# QuadQuantizer.net
KiCad netlist of a schematic drawn in EAGLE
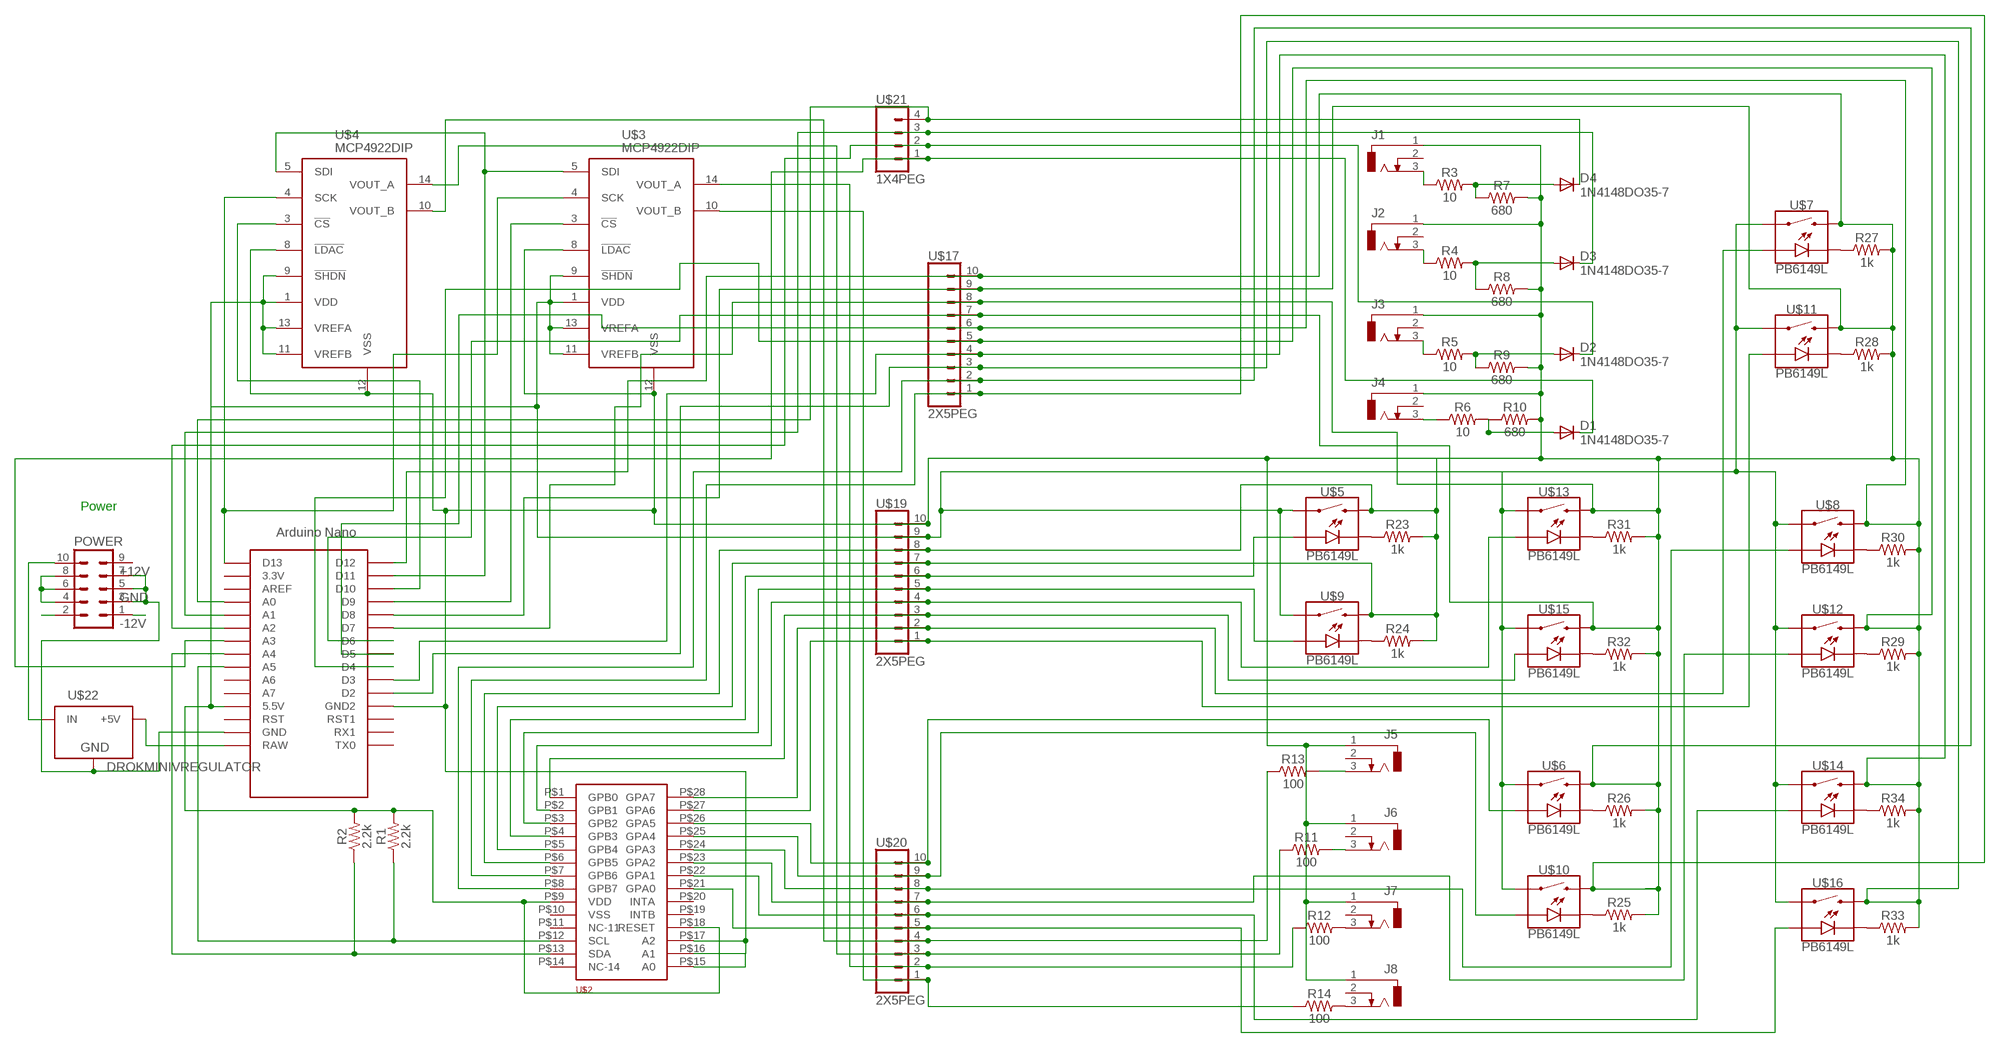
[diagram p0: schematic, sheet 1]

(export (version "E")
  (design (tool "Eeschema 10.0.6"))
  (components
    (comp (ref "D1")
      (value "1N4148DO35-7")
      (footprint "eagle-import:DO35-7")
      (libsource (lib "eagle-import") (part "1N4148DO35-7"))
    )
    (comp (ref "D2")
      (value "1N4148DO35-7")
      (footprint "eagle-import:DO35-7")
      (libsource (lib "eagle-import") (part "1N4148DO35-7"))
    )
    (comp (ref "D3")
      (value "1N4148DO35-7")
      (footprint "eagle-import:DO35-7")
      (libsource (lib "eagle-import") (part "1N4148DO35-7"))
    )
    (comp (ref "D4")
      (value "1N4148DO35-7")
      (footprint "eagle-import:DO35-7")
      (libsource (lib "eagle-import") (part "1N4148DO35-7"))
    )
    (comp (ref "J1")
      (value "THONK35A")
      (footprint "eagle-import:THONK35A")
      (libsource (lib "eagle-import") (part "THONK35A"))
    )
    (comp (ref "J2")
      (value "THONK35A")
      (footprint "eagle-import:THONK35A")
      (libsource (lib "eagle-import") (part "THONK35A"))
    )
    (comp (ref "J3")
      (value "THONK35A")
      (footprint "eagle-import:THONK35A")
      (libsource (lib "eagle-import") (part "THONK35A"))
    )
    (comp (ref "J4")
      (value "THONK35A")
      (footprint "eagle-import:THONK35A")
      (libsource (lib "eagle-import") (part "THONK35A"))
    )
    (comp (ref "J5")
      (value "THONK35A")
      (footprint "eagle-import:THONK35A")
      (libsource (lib "eagle-import") (part "THONK35A"))
    )
    (comp (ref "J6")
      (value "THONK35A")
      (footprint "eagle-import:THONK35A")
      (libsource (lib "eagle-import") (part "THONK35A"))
    )
    (comp (ref "J7")
      (value "THONK35A")
      (footprint "eagle-import:THONK35A")
      (libsource (lib "eagle-import") (part "THONK35A"))
    )
    (comp (ref "J8")
      (value "THONK35A")
      (footprint "eagle-import:THONK35A")
      (libsource (lib "eagle-import") (part "THONK35A"))
    )
    (comp (ref "POWER")
      (value "10_PIN_HEADER")
      (footprint "eagle-import:MA05-2")
      (libsource (lib "eagle-import") (part "10_PIN_HEADER"))
    )
    (comp (ref "R1")
      (value "2.2k")
      (footprint "eagle-import:AXIAL-0.3")
      (libsource (lib "eagle-import") (part "1KOHM-HORIZ-1/4W-1%"))
    )
    (comp (ref "R2")
      (value "2.2k")
      (footprint "eagle-import:AXIAL-0.3")
      (libsource (lib "eagle-import") (part "1KOHM-HORIZ-1/4W-1%"))
    )
    (comp (ref "R3")
      (value "10")
      (footprint "eagle-import:AXIAL-0.3")
      (libsource (lib "eagle-import") (part "10OHM-HORIZ-1/4W-1%"))
    )
    (comp (ref "R4")
      (value "10")
      (footprint "eagle-import:AXIAL-0.3")
      (libsource (lib "eagle-import") (part "10OHM-HORIZ-1/4W-1%"))
    )
    (comp (ref "R5")
      (value "10")
      (footprint "eagle-import:AXIAL-0.3")
      (libsource (lib "eagle-import") (part "10OHM-HORIZ-1/4W-1%"))
    )
    (comp (ref "R6")
      (value "10")
      (footprint "eagle-import:AXIAL-0.3")
      (libsource (lib "eagle-import") (part "10OHM-HORIZ-1/4W-1%"))
    )
    (comp (ref "R7")
      (value "680")
      (footprint "eagle-import:AXIAL-0.3")
      (libsource (lib "eagle-import") (part "10OHM-HORIZ-1/4W-1%"))
    )
    (comp (ref "R8")
      (value "680")
      (footprint "eagle-import:AXIAL-0.3")
      (libsource (lib "eagle-import") (part "10OHM-HORIZ-1/4W-1%"))
    )
    (comp (ref "R9")
      (value "680")
      (footprint "eagle-import:AXIAL-0.3")
      (libsource (lib "eagle-import") (part "10OHM-HORIZ-1/4W-1%"))
    )
    (comp (ref "R10")
      (value "680")
      (footprint "eagle-import:AXIAL-0.3")
      (libsource (lib "eagle-import") (part "10OHM-HORIZ-1/4W-1%"))
    )
    (comp (ref "R11")
      (value "100")
      (footprint "eagle-import:AXIAL-0.3")
      (libsource (lib "eagle-import") (part "100OHM-HORIZ-1/4W-1%"))
    )
    (comp (ref "R12")
      (value "100")
      (footprint "eagle-import:AXIAL-0.3")
      (libsource (lib "eagle-import") (part "100OHM-HORIZ-1/4W-1%"))
    )
    (comp (ref "R13")
      (value "100")
      (footprint "eagle-import:AXIAL-0.3")
      (libsource (lib "eagle-import") (part "100OHM-HORIZ-1/4W-1%"))
    )
    (comp (ref "R14")
      (value "100")
      (footprint "eagle-import:AXIAL-0.3")
      (libsource (lib "eagle-import") (part "100OHM-HORIZ-1/4W-1%"))
    )
    (comp (ref "R23")
      (value "1k")
      (footprint "eagle-import:AXIAL-0.3")
      (libsource (lib "eagle-import") (part "1KOHM-HORIZ-1/4W-1%"))
    )
    (comp (ref "R24")
      (value "1k")
      (footprint "eagle-import:AXIAL-0.3")
      (libsource (lib "eagle-import") (part "1KOHM-HORIZ-1/4W-1%"))
    )
    (comp (ref "R25")
      (value "1k")
      (footprint "eagle-import:AXIAL-0.3")
      (libsource (lib "eagle-import") (part "1KOHM-HORIZ-1/4W-1%"))
    )
    (comp (ref "R26")
      (value "1k")
      (footprint "eagle-import:AXIAL-0.3")
      (libsource (lib "eagle-import") (part "1KOHM-HORIZ-1/4W-1%"))
    )
    (comp (ref "R27")
      (value "1k")
      (footprint "eagle-import:AXIAL-0.3")
      (libsource (lib "eagle-import") (part "1KOHM-HORIZ-1/4W-1%"))
    )
    (comp (ref "R28")
      (value "1k")
      (footprint "eagle-import:AXIAL-0.3")
      (libsource (lib "eagle-import") (part "1KOHM-HORIZ-1/4W-1%"))
    )
    (comp (ref "R29")
      (value "1k")
      (footprint "eagle-import:AXIAL-0.3")
      (libsource (lib "eagle-import") (part "1KOHM-HORIZ-1/4W-1%"))
    )
    (comp (ref "R30")
      (value "1k")
      (footprint "eagle-import:AXIAL-0.3")
      (libsource (lib "eagle-import") (part "1KOHM-HORIZ-1/4W-1%"))
    )
    (comp (ref "R31")
      (value "1k")
      (footprint "eagle-import:AXIAL-0.3")
      (libsource (lib "eagle-import") (part "1KOHM-HORIZ-1/4W-1%"))
    )
    (comp (ref "R32")
      (value "1k")
      (footprint "eagle-import:AXIAL-0.3")
      (libsource (lib "eagle-import") (part "1KOHM-HORIZ-1/4W-1%"))
    )
    (comp (ref "R33")
      (value "1k")
      (footprint "eagle-import:AXIAL-0.3")
      (libsource (lib "eagle-import") (part "1KOHM-HORIZ-1/4W-1%"))
    )
    (comp (ref "R34")
      (value "1k")
      (footprint "eagle-import:AXIAL-0.3")
      (libsource (lib "eagle-import") (part "1KOHM-HORIZ-1/4W-1%"))
    )
    (comp (ref "U$1")
      (value "NANO")
      (footprint "eagle-import:NANO")
      (libsource (lib "eagle-import") (part "NANO"))
    )
    (comp (ref "U$2")
      (value "MCP23017-E/SP")
      (footprint "eagle-import:DIP28")
      (libsource (lib "eagle-import") (part "MCP23017-E/SP"))
    )
    (comp (ref "U$3")
      (value "MCP4922DIP")
      (footprint "eagle-import:EDG-07")
      (libsource (lib "eagle-import") (part "MCP4922DIP"))
    )
    (comp (ref "U$4")
      (value "MCP4922DIP")
      (footprint "eagle-import:EDG-07")
      (libsource (lib "eagle-import") (part "MCP4922DIP"))
    )
    (comp (ref "U$5")
      (value "PB6149L")
      (footprint "eagle-import:PB6149L")
      (libsource (lib "eagle-import") (part "PB6149L"))
    )
    (comp (ref "U$6")
      (value "PB6149L")
      (footprint "eagle-import:PB6149L")
      (libsource (lib "eagle-import") (part "PB6149L"))
    )
    (comp (ref "U$7")
      (value "PB6149L")
      (footprint "eagle-import:PB6149L")
      (libsource (lib "eagle-import") (part "PB6149L"))
    )
    (comp (ref "U$8")
      (value "PB6149L")
      (footprint "eagle-import:PB6149L")
      (libsource (lib "eagle-import") (part "PB6149L"))
    )
    (comp (ref "U$9")
      (value "PB6149L")
      (footprint "eagle-import:PB6149L")
      (libsource (lib "eagle-import") (part "PB6149L"))
    )
    (comp (ref "U$10")
      (value "PB6149L")
      (footprint "eagle-import:PB6149L")
      (libsource (lib "eagle-import") (part "PB6149L"))
    )
    (comp (ref "U$11")
      (value "PB6149L")
      (footprint "eagle-import:PB6149L")
      (libsource (lib "eagle-import") (part "PB6149L"))
    )
    (comp (ref "U$12")
      (value "PB6149L")
      (footprint "eagle-import:PB6149L")
      (libsource (lib "eagle-import") (part "PB6149L"))
    )
    (comp (ref "U$13")
      (value "PB6149L")
      (footprint "eagle-import:PB6149L")
      (libsource (lib "eagle-import") (part "PB6149L"))
    )
    (comp (ref "U$14")
      (value "PB6149L")
      (footprint "eagle-import:PB6149L")
      (libsource (lib "eagle-import") (part "PB6149L"))
    )
    (comp (ref "U$15")
      (value "PB6149L")
      (footprint "eagle-import:PB6149L")
      (libsource (lib "eagle-import") (part "PB6149L"))
    )
    (comp (ref "U$16")
      (value "PB6149L")
      (footprint "eagle-import:PB6149L")
      (libsource (lib "eagle-import") (part "PB6149L"))
    )
    (comp (ref "U$17")
      (value "2X5PEG")
      (footprint "eagle-import:2X5")
      (libsource (lib "eagle-import") (part "2X5PEG"))
    )
    (comp (ref "U$19")
      (value "2X5PEG")
      (footprint "eagle-import:2X5")
      (libsource (lib "eagle-import") (part "2X5PEG"))
    )
    (comp (ref "U$20")
      (value "2X5PEG")
      (footprint "eagle-import:2X5")
      (libsource (lib "eagle-import") (part "2X5PEG"))
    )
    (comp (ref "U$21")
      (value "1X4PEG")
      (footprint "eagle-import:1X04")
      (libsource (lib "eagle-import") (part "1X4PEG"))
    )
    (comp (ref "U$22")
      (value "DROKMINIVREGULATOR")
      (footprint "eagle-import:1X04")
      (libsource (lib "eagle-import") (part "DROKMINIVREGULATOR"))
    )
  )
  (nets
    (net (code "1") (name "+12V") (class "Default")
      (node (ref "POWER") (pin "10") (pinfunction "10_10") (pintype "passive"))
      (node (ref "U$22") (pin "2") (pinfunction "IN_2") (pintype "power_in"))
    )
    (net (code "2") (name "-12V") (class "Default")
      (node (ref "POWER") (pin "1") (pinfunction "1_1") (pintype "passive"))
      (node (ref "POWER") (pin "2") (pinfunction "2_2") (pintype "passive"))
    )
    (net (code "3") (name "GND") (class "Default")
      (node (ref "POWER") (pin "3") (pinfunction "3_3") (pintype "passive"))
      (node (ref "POWER") (pin "4") (pinfunction "4_4") (pintype "passive"))
      (node (ref "POWER") (pin "5") (pinfunction "5_5") (pintype "passive"))
      (node (ref "POWER") (pin "6") (pinfunction "6_6") (pintype "passive"))
      (node (ref "POWER") (pin "7") (pinfunction "7_7") (pintype "passive"))
      (node (ref "POWER") (pin "8") (pinfunction "8_8") (pintype "passive"))
      (node (ref "U$1") (pin "GND") (pinfunction "GND_GND") (pintype "bidirectional"))
      (node (ref "U$22") (pin "3") (pinfunction "GND_3") (pintype "power_in"))
    )
    (net (code "4") (name "Net-(D1-PadC)") (class "Default")
      (node (ref "D1") (pin "C") (pinfunction "C_C") (pintype "passive"))
      (node (ref "U$1") (pin "A3") (pinfunction "A3_A3") (pintype "bidirectional"))
      (node (ref "U$21") (pin "1") (pinfunction "1_1") (pintype "passive"))
    )
    (net (code "5") (name "Net-(D2-PadC)") (class "Default")
      (node (ref "D2") (pin "C") (pinfunction "C_C") (pintype "passive"))
      (node (ref "U$1") (pin "A2") (pinfunction "A2_A2") (pintype "bidirectional"))
      (node (ref "U$21") (pin "2") (pinfunction "2_2") (pintype "passive"))
    )
    (net (code "6") (name "Net-(D3-PadC)") (class "Default")
      (node (ref "D3") (pin "C") (pinfunction "C_C") (pintype "passive"))
      (node (ref "U$1") (pin "A1") (pinfunction "A1_A1") (pintype "bidirectional"))
      (node (ref "U$21") (pin "3") (pinfunction "3_3") (pintype "passive"))
    )
    (net (code "7") (name "Net-(D4-PadC)") (class "Default")
      (node (ref "D4") (pin "C") (pinfunction "C_C") (pintype "passive"))
      (node (ref "U$1") (pin "A0") (pinfunction "A0_A0") (pintype "bidirectional"))
      (node (ref "U$21") (pin "4") (pinfunction "4_4") (pintype "passive"))
    )
    (net (code "8") (name "Net-(R1-1)") (class "Default")
      (node (ref "R1") (pin "P$1") (pinfunction "1_P$1") (pintype "passive"))
      (node (ref "U$1") (pin "A5") (pinfunction "A5_A5") (pintype "bidirectional"))
      (node (ref "U$2") (pin "P$12") (pinfunction "SCL_P$12") (pintype "bidirectional"))
    )
    (net (code "9") (name "Net-(R1-2)") (class "Default")
      (node (ref "R1") (pin "P$2") (pinfunction "2_P$2") (pintype "passive"))
      (node (ref "R2") (pin "P$2") (pinfunction "2_P$2") (pintype "passive"))
      (node (ref "U$1") (pin "5V") (pinfunction "5.5V_5V") (pintype "bidirectional"))
      (node (ref "U$10") (pin "P$1") (pinfunction "1_P$1") (pintype "passive"))
      (node (ref "U$11") (pin "P$1") (pinfunction "1_P$1") (pintype "passive"))
      (node (ref "U$12") (pin "P$1") (pinfunction "1_P$1") (pintype "passive"))
      (node (ref "U$13") (pin "P$1") (pinfunction "1_P$1") (pintype "passive"))
      (node (ref "U$14") (pin "P$1") (pinfunction "1_P$1") (pintype "passive"))
      (node (ref "U$15") (pin "P$1") (pinfunction "1_P$1") (pintype "passive"))
      (node (ref "U$16") (pin "P$1") (pinfunction "1_P$1") (pintype "passive"))
      (node (ref "U$19") (pin "9") (pinfunction "9_9") (pintype "passive"))
      (node (ref "U$2") (pin "P$18") (pinfunction "RESET_P$18") (pintype "bidirectional"))
      (node (ref "U$2") (pin "P$9") (pinfunction "VDD_P$9") (pintype "bidirectional"))
      (node (ref "U$3") (pin "1") (pinfunction "VDD_1") (pintype "bidirectional"))
      (node (ref "U$3") (pin "11") (pinfunction "VREFB_11") (pintype "bidirectional"))
      (node (ref "U$3") (pin "13") (pinfunction "VREFA_13") (pintype "bidirectional"))
      (node (ref "U$3") (pin "9") (pinfunction "~{SHDN}_9") (pintype "bidirectional"))
      (node (ref "U$4") (pin "1") (pinfunction "VDD_1") (pintype "bidirectional"))
      (node (ref "U$4") (pin "11") (pinfunction "VREFB_11") (pintype "bidirectional"))
      (node (ref "U$4") (pin "13") (pinfunction "VREFA_13") (pintype "bidirectional"))
      (node (ref "U$4") (pin "9") (pinfunction "~{SHDN}_9") (pintype "bidirectional"))
      (node (ref "U$5") (pin "P$1") (pinfunction "1_P$1") (pintype "passive"))
      (node (ref "U$6") (pin "P$1") (pinfunction "1_P$1") (pintype "passive"))
      (node (ref "U$7") (pin "P$1") (pinfunction "1_P$1") (pintype "passive"))
      (node (ref "U$8") (pin "P$1") (pinfunction "1_P$1") (pintype "passive"))
      (node (ref "U$9") (pin "P$1") (pinfunction "1_P$1") (pintype "passive"))
    )
    (net (code "10") (name "Net-(R2-1)") (class "Default")
      (node (ref "R2") (pin "P$1") (pinfunction "1_P$1") (pintype "passive"))
      (node (ref "U$1") (pin "A4") (pinfunction "A4_A4") (pintype "bidirectional"))
      (node (ref "U$2") (pin "P$13") (pinfunction "SDA_P$13") (pintype "bidirectional"))
    )
    (net (code "11") (name "Net-(R3-1)") (class "Default")
      (node (ref "J1") (pin "3") (pinfunction "3_3") (pintype "passive"))
      (node (ref "R3") (pin "P$1") (pinfunction "1_P$1") (pintype "passive"))
    )
    (net (code "12") (name "Net-(R3-2)") (class "Default")
      (node (ref "D4") (pin "A") (pinfunction "A_A") (pintype "passive"))
      (node (ref "R3") (pin "P$2") (pinfunction "2_P$2") (pintype "passive"))
      (node (ref "R7") (pin "P$1") (pinfunction "1_P$1") (pintype "passive"))
    )
    (net (code "13") (name "Net-(R4-1)") (class "Default")
      (node (ref "J2") (pin "3") (pinfunction "3_3") (pintype "passive"))
      (node (ref "R4") (pin "P$1") (pinfunction "1_P$1") (pintype "passive"))
    )
    (net (code "14") (name "Net-(R4-2)") (class "Default")
      (node (ref "D3") (pin "A") (pinfunction "A_A") (pintype "passive"))
      (node (ref "R4") (pin "P$2") (pinfunction "2_P$2") (pintype "passive"))
      (node (ref "R8") (pin "P$1") (pinfunction "1_P$1") (pintype "passive"))
    )
    (net (code "15") (name "Net-(R5-1)") (class "Default")
      (node (ref "J3") (pin "3") (pinfunction "3_3") (pintype "passive"))
      (node (ref "R5") (pin "P$1") (pinfunction "1_P$1") (pintype "passive"))
    )
    (net (code "16") (name "Net-(R5-2)") (class "Default")
      (node (ref "D2") (pin "A") (pinfunction "A_A") (pintype "passive"))
      (node (ref "R5") (pin "P$2") (pinfunction "2_P$2") (pintype "passive"))
      (node (ref "R9") (pin "P$1") (pinfunction "1_P$1") (pintype "passive"))
    )
    (net (code "17") (name "Net-(R6-1)") (class "Default")
      (node (ref "J4") (pin "3") (pinfunction "3_3") (pintype "passive"))
      (node (ref "R6") (pin "P$1") (pinfunction "1_P$1") (pintype "passive"))
    )
    (net (code "18") (name "Net-(R10-1)") (class "Default")
      (node (ref "D1") (pin "A") (pinfunction "A_A") (pintype "passive"))
      (node (ref "R10") (pin "P$1") (pinfunction "1_P$1") (pintype "passive"))
      (node (ref "R6") (pin "P$2") (pinfunction "2_P$2") (pintype "passive"))
    )
    (net (code "19") (name "Net-(R10-2)") (class "Default")
      (node (ref "J1") (pin "1") (pinfunction "1_1") (pintype "passive"))
      (node (ref "J2") (pin "1") (pinfunction "1_1") (pintype "passive"))
      (node (ref "J3") (pin "1") (pinfunction "1_1") (pintype "passive"))
      (node (ref "J4") (pin "1") (pinfunction "1_1") (pintype "passive"))
      (node (ref "J5") (pin "1") (pinfunction "1_1") (pintype "passive"))
      (node (ref "J6") (pin "1") (pinfunction "1_1") (pintype "passive"))
      (node (ref "J7") (pin "1") (pinfunction "1_1") (pintype "passive"))
      (node (ref "J8") (pin "1") (pinfunction "1_1") (pintype "passive"))
      (node (ref "R10") (pin "P$2") (pinfunction "2_P$2") (pintype "passive"))
      (node (ref "R23") (pin "P$2") (pinfunction "2_P$2") (pintype "passive"))
      (node (ref "R24") (pin "P$2") (pinfunction "2_P$2") (pintype "passive"))
      (node (ref "R25") (pin "P$2") (pinfunction "2_P$2") (pintype "passive"))
      (node (ref "R26") (pin "P$2") (pinfunction "2_P$2") (pintype "passive"))
      (node (ref "R27") (pin "P$2") (pinfunction "2_P$2") (pintype "passive"))
      (node (ref "R28") (pin "P$2") (pinfunction "2_P$2") (pintype "passive"))
      (node (ref "R29") (pin "P$2") (pinfunction "2_P$2") (pintype "passive"))
      (node (ref "R30") (pin "P$2") (pinfunction "2_P$2") (pintype "passive"))
      (node (ref "R31") (pin "P$2") (pinfunction "2_P$2") (pintype "passive"))
      (node (ref "R32") (pin "P$2") (pinfunction "2_P$2") (pintype "passive"))
      (node (ref "R33") (pin "P$2") (pinfunction "2_P$2") (pintype "passive"))
      (node (ref "R34") (pin "P$2") (pinfunction "2_P$2") (pintype "passive"))
      (node (ref "R7") (pin "P$2") (pinfunction "2_P$2") (pintype "passive"))
      (node (ref "R8") (pin "P$2") (pinfunction "2_P$2") (pintype "passive"))
      (node (ref "R9") (pin "P$2") (pinfunction "2_P$2") (pintype "passive"))
      (node (ref "U$1") (pin "D12") (pinfunction "D12_D12") (pintype "bidirectional"))
      (node (ref "U$1") (pin "D2") (pinfunction "D2_D2") (pintype "bidirectional"))
      (node (ref "U$1") (pin "D3") (pinfunction "D3_D3") (pintype "bidirectional"))
      (node (ref "U$1") (pin "D4") (pinfunction "D4_D4") (pintype "bidirectional"))
      (node (ref "U$1") (pin "D5") (pinfunction "D5_D5") (pintype "bidirectional"))
      (node (ref "U$1") (pin "D6") (pinfunction "D6_D6") (pintype "bidirectional"))
      (node (ref "U$1") (pin "D7") (pinfunction "D7_D7") (pintype "bidirectional"))
      (node (ref "U$1") (pin "D8") (pinfunction "D8_D8") (pintype "bidirectional"))
      (node (ref "U$1") (pin "GND1") (pinfunction "GND2_GND1") (pintype "bidirectional"))
      (node (ref "U$10") (pin "P$3") (pinfunction "2_P$3") (pintype "passive"))
      (node (ref "U$11") (pin "P$3") (pinfunction "2_P$3") (pintype "passive"))
      (node (ref "U$12") (pin "P$3") (pinfunction "2_P$3") (pintype "passive"))
      (node (ref "U$13") (pin "P$3") (pinfunction "2_P$3") (pintype "passive"))
      (node (ref "U$14") (pin "P$3") (pinfunction "2_P$3") (pintype "passive"))
      (node (ref "U$15") (pin "P$3") (pinfunction "2_P$3") (pintype "passive"))
      (node (ref "U$16") (pin "P$3") (pinfunction "2_P$3") (pintype "passive"))
      (node (ref "U$17") (pin "1") (pinfunction "1_1") (pintype "passive"))
      (node (ref "U$17") (pin "10") (pinfunction "10_10") (pintype "passive"))
      (node (ref "U$17") (pin "2") (pinfunction "2_2") (pintype "passive"))
      (node (ref "U$17") (pin "3") (pinfunction "3_3") (pintype "passive"))
      (node (ref "U$17") (pin "4") (pinfunction "4_4") (pintype "passive"))
      (node (ref "U$17") (pin "5") (pinfunction "5_5") (pintype "passive"))
      (node (ref "U$17") (pin "6") (pinfunction "6_6") (pintype "passive"))
      (node (ref "U$17") (pin "7") (pinfunction "7_7") (pintype "passive"))
      (node (ref "U$17") (pin "8") (pinfunction "8_8") (pintype "passive"))
      (node (ref "U$17") (pin "9") (pinfunction "9_9") (pintype "passive"))
      (node (ref "U$19") (pin "10") (pinfunction "10_10") (pintype "passive"))
      (node (ref "U$19") (pin "7") (pinfunction "7_7") (pintype "passive"))
      (node (ref "U$19") (pin "8") (pinfunction "8_8") (pintype "passive"))
      (node (ref "U$2") (pin "P$15") (pinfunction "A0_P$15") (pintype "bidirectional"))
      (node (ref "U$2") (pin "P$16") (pinfunction "A1_P$16") (pintype "bidirectional"))
      (node (ref "U$2") (pin "P$17") (pinfunction "A2_P$17") (pintype "bidirectional"))
      (node (ref "U$2") (pin "P$5") (pinfunction "GPB4_P$5") (pintype "bidirectional"))
      (node (ref "U$2") (pin "P$6") (pinfunction "GPB5_P$6") (pintype "bidirectional"))
      (node (ref "U$2") (pin "P$7") (pinfunction "GPB6_P$7") (pintype "bidirectional"))
      (node (ref "U$2") (pin "P$8") (pinfunction "GPB7_P$8") (pintype "bidirectional"))
      (node (ref "U$3") (pin "12") (pinfunction "VSS_12") (pintype "bidirectional"))
      (node (ref "U$3") (pin "8") (pinfunction "~{LDAC}_8") (pintype "bidirectional"))
      (node (ref "U$4") (pin "12") (pinfunction "VSS_12") (pintype "bidirectional"))
      (node (ref "U$4") (pin "8") (pinfunction "~{LDAC}_8") (pintype "bidirectional"))
      (node (ref "U$5") (pin "P$3") (pinfunction "2_P$3") (pintype "passive"))
      (node (ref "U$6") (pin "P$3") (pinfunction "2_P$3") (pintype "passive"))
      (node (ref "U$7") (pin "P$3") (pinfunction "2_P$3") (pintype "passive"))
      (node (ref "U$8") (pin "P$3") (pinfunction "2_P$3") (pintype "passive"))
      (node (ref "U$9") (pin "P$3") (pinfunction "2_P$3") (pintype "passive"))
    )
    (net (code "20") (name "Net-(R11-1)") (class "Default")
      (node (ref "R11") (pin "P$1") (pinfunction "1_P$1") (pintype "passive"))
      (node (ref "U$20") (pin "3") (pinfunction "3_3") (pintype "passive"))
      (node (ref "U$4") (pin "14") (pinfunction "VOUT_A_14") (pintype "bidirectional"))
    )
    (net (code "21") (name "Net-(R11-2)") (class "Default")
      (node (ref "J6") (pin "3") (pinfunction "3_3") (pintype "passive"))
      (node (ref "R11") (pin "P$2") (pinfunction "2_P$2") (pintype "passive"))
    )
    (net (code "22") (name "Net-(R12-1)") (class "Default")
      (node (ref "R12") (pin "P$1") (pinfunction "1_P$1") (pintype "passive"))
      (node (ref "U$20") (pin "2") (pinfunction "2_2") (pintype "passive"))
      (node (ref "U$3") (pin "14") (pinfunction "VOUT_A_14") (pintype "bidirectional"))
    )
    (net (code "23") (name "Net-(R12-2)") (class "Default")
      (node (ref "J7") (pin "3") (pinfunction "3_3") (pintype "passive"))
      (node (ref "R12") (pin "P$2") (pinfunction "2_P$2") (pintype "passive"))
    )
    (net (code "24") (name "Net-(R13-1)") (class "Default")
      (node (ref "R13") (pin "P$1") (pinfunction "1_P$1") (pintype "passive"))
      (node (ref "U$20") (pin "4") (pinfunction "4_4") (pintype "passive"))
      (node (ref "U$4") (pin "10") (pinfunction "VOUT_B_10") (pintype "bidirectional"))
    )
    (net (code "25") (name "Net-(R13-2)") (class "Default")
      (node (ref "J5") (pin "3") (pinfunction "3_3") (pintype "passive"))
      (node (ref "R13") (pin "P$2") (pinfunction "2_P$2") (pintype "passive"))
    )
    (net (code "26") (name "Net-(R14-1)") (class "Default")
      (node (ref "R14") (pin "P$1") (pinfunction "1_P$1") (pintype "passive"))
      (node (ref "U$20") (pin "1") (pinfunction "1_1") (pintype "passive"))
      (node (ref "U$3") (pin "10") (pinfunction "VOUT_B_10") (pintype "bidirectional"))
    )
    (net (code "27") (name "Net-(R14-2)") (class "Default")
      (node (ref "J8") (pin "3") (pinfunction "3_3") (pintype "passive"))
      (node (ref "R14") (pin "P$2") (pinfunction "2_P$2") (pintype "passive"))
    )
    (net (code "28") (name "Net-(R23-1)") (class "Default")
      (node (ref "R23") (pin "P$1") (pinfunction "1_P$1") (pintype "passive"))
      (node (ref "U$5") (pin "P$5") (pinfunction "C_P$5") (pintype "passive"))
    )
    (net (code "29") (name "Net-(R24-1)") (class "Default")
      (node (ref "R24") (pin "P$1") (pinfunction "1_P$1") (pintype "passive"))
      (node (ref "U$9") (pin "P$5") (pinfunction "C_P$5") (pintype "passive"))
    )
    (net (code "30") (name "Net-(R25-1)") (class "Default")
      (node (ref "R25") (pin "P$1") (pinfunction "1_P$1") (pintype "passive"))
      (node (ref "U$10") (pin "P$5") (pinfunction "C_P$5") (pintype "passive"))
    )
    (net (code "31") (name "Net-(R26-1)") (class "Default")
      (node (ref "R26") (pin "P$1") (pinfunction "1_P$1") (pintype "passive"))
      (node (ref "U$6") (pin "P$5") (pinfunction "C_P$5") (pintype "passive"))
    )
    (net (code "32") (name "Net-(R27-1)") (class "Default")
      (node (ref "R27") (pin "P$1") (pinfunction "1_P$1") (pintype "passive"))
      (node (ref "U$7") (pin "P$5") (pinfunction "C_P$5") (pintype "passive"))
    )
    (net (code "33") (name "Net-(R28-1)") (class "Default")
      (node (ref "R28") (pin "P$1") (pinfunction "1_P$1") (pintype "passive"))
      (node (ref "U$11") (pin "P$5") (pinfunction "C_P$5") (pintype "passive"))
    )
    (net (code "34") (name "Net-(R29-1)") (class "Default")
      (node (ref "R29") (pin "P$1") (pinfunction "1_P$1") (pintype "passive"))
      (node (ref "U$12") (pin "P$5") (pinfunction "C_P$5") (pintype "passive"))
    )
    (net (code "35") (name "Net-(R30-1)") (class "Default")
      (node (ref "R30") (pin "P$1") (pinfunction "1_P$1") (pintype "passive"))
      (node (ref "U$8") (pin "P$5") (pinfunction "C_P$5") (pintype "passive"))
    )
    (net (code "36") (name "Net-(R31-1)") (class "Default")
      (node (ref "R31") (pin "P$1") (pinfunction "1_P$1") (pintype "passive"))
      (node (ref "U$13") (pin "P$5") (pinfunction "C_P$5") (pintype "passive"))
    )
    (net (code "37") (name "Net-(R32-1)") (class "Default")
      (node (ref "R32") (pin "P$1") (pinfunction "1_P$1") (pintype "passive"))
      (node (ref "U$15") (pin "P$5") (pinfunction "C_P$5") (pintype "passive"))
    )
    (net (code "38") (name "Net-(R33-1)") (class "Default")
      (node (ref "R33") (pin "P$1") (pinfunction "1_P$1") (pintype "passive"))
      (node (ref "U$16") (pin "P$5") (pinfunction "C_P$5") (pintype "passive"))
    )
    (net (code "39") (name "Net-(R34-1)") (class "Default")
      (node (ref "R34") (pin "P$1") (pinfunction "1_P$1") (pintype "passive"))
      (node (ref "U$14") (pin "P$5") (pinfunction "C_P$5") (pintype "passive"))
    )
    (net (code "40") (name "Net-(U$2-GPA3)") (class "Default")
      (node (ref "U$2") (pin "P$24") (pinfunction "GPA3_P$24") (pintype "bidirectional"))
      (node (ref "U$20") (pin "8") (pinfunction "8_8") (pintype "passive"))
      (node (ref "U$8") (pin "P$2") (pinfunction "A_P$2") (pintype "passive"))
    )
    (net (code "41") (name "Net-(U$2-GPA5)") (class "Default")
      (node (ref "U$2") (pin "P$26") (pinfunction "GPA5_P$26") (pintype "bidirectional"))
      (node (ref "U$20") (pin "10") (pinfunction "10_10") (pintype "passive"))
      (node (ref "U$6") (pin "P$2") (pinfunction "A_P$2") (pintype "passive"))
    )
    (net (code "42") (name "Net-(U$2-GPA7)") (class "Default")
      (node (ref "U$19") (pin "2") (pinfunction "2_2") (pintype "passive"))
      (node (ref "U$2") (pin "P$28") (pinfunction "GPA7_P$28") (pintype "bidirectional"))
      (node (ref "U$7") (pin "P$2") (pinfunction "A_P$2") (pintype "passive"))
    )
    (net (code "43") (name "Net-(U$2-GPB2)") (class "Default")
      (node (ref "U$19") (pin "5") (pinfunction "5_5") (pintype "passive"))
      (node (ref "U$2") (pin "P$3") (pinfunction "GPB2_P$3") (pintype "bidirectional"))
      (node (ref "U$9") (pin "P$2") (pinfunction "A_P$2") (pintype "passive"))
    )
    (net (code "44") (name "Net-(U$2-GPB3)") (class "Default")
      (node (ref "U$19") (pin "6") (pinfunction "6_6") (pintype "passive"))
      (node (ref "U$2") (pin "P$4") (pinfunction "GPB3_P$4") (pintype "bidirectional"))
      (node (ref "U$5") (pin "P$2") (pinfunction "A_P$2") (pintype "passive"))
    )
    (net (code "45") (name "Net-(U$3-SCK)") (class "Default")
      (node (ref "U$1") (pin "D13") (pinfunction "D13_D13") (pintype "bidirectional"))
      (node (ref "U$3") (pin "4") (pinfunction "SCK_4") (pintype "bidirectional"))
      (node (ref "U$4") (pin "4") (pinfunction "SCK_4") (pintype "bidirectional"))
    )
    (net (code "46") (name "Net-(U$3-SDI)") (class "Default")
      (node (ref "U$1") (pin "D11") (pinfunction "D11_D11") (pintype "bidirectional"))
      (node (ref "U$3") (pin "5") (pinfunction "SDI_5") (pintype "bidirectional"))
      (node (ref "U$4") (pin "5") (pinfunction "SDI_5") (pintype "bidirectional"))
    )
    (net (code "47") (name "Net-(U$3-~{CS})") (class "Default")
      (node (ref "U$1") (pin "D9") (pinfunction "D9_D9") (pintype "bidirectional"))
      (node (ref "U$3") (pin "3") (pinfunction "~{CS}_3") (pintype "bidirectional"))
    )
    (net (code "48") (name "Net-(U$4-~{CS})") (class "Default")
      (node (ref "U$1") (pin "D10") (pinfunction "D10_D10") (pintype "bidirectional"))
      (node (ref "U$4") (pin "3") (pinfunction "~{CS}_3") (pintype "bidirectional"))
    )
    (net (code "49") (name "Net-(U$10-A)") (class "Default")
      (node (ref "U$10") (pin "P$2") (pinfunction "A_P$2") (pintype "passive"))
      (node (ref "U$2") (pin "P$25") (pinfunction "GPA4_P$25") (pintype "bidirectional"))
      (node (ref "U$20") (pin "9") (pinfunction "9_9") (pintype "passive"))
    )
    (net (code "50") (name "Net-(U$11-A)") (class "Default")
      (node (ref "U$11") (pin "P$2") (pinfunction "A_P$2") (pintype "passive"))
      (node (ref "U$19") (pin "1") (pinfunction "1_1") (pintype "passive"))
      (node (ref "U$2") (pin "P$27") (pinfunction "GPA6_P$27") (pintype "bidirectional"))
    )
    (net (code "51") (name "Net-(U$12-A)") (class "Default")
      (node (ref "U$12") (pin "P$2") (pinfunction "A_P$2") (pintype "passive"))
      (node (ref "U$2") (pin "P$23") (pinfunction "GPA2_P$23") (pintype "bidirectional"))
      (node (ref "U$20") (pin "7") (pinfunction "7_7") (pintype "passive"))
    )
    (net (code "52") (name "Net-(U$13-A)") (class "Default")
      (node (ref "U$13") (pin "P$2") (pinfunction "A_P$2") (pintype "passive"))
      (node (ref "U$19") (pin "4") (pinfunction "4_4") (pintype "passive"))
      (node (ref "U$2") (pin "P$2") (pinfunction "GPB1_P$2") (pintype "bidirectional"))
    )
    (net (code "53") (name "Net-(U$14-A)") (class "Default")
      (node (ref "U$14") (pin "P$2") (pinfunction "A_P$2") (pintype "passive"))
      (node (ref "U$2") (pin "P$22") (pinfunction "GPA1_P$22") (pintype "bidirectional"))
      (node (ref "U$20") (pin "6") (pinfunction "6_6") (pintype "passive"))
    )
    (net (code "54") (name "Net-(U$15-A)") (class "Default")
      (node (ref "U$15") (pin "P$2") (pinfunction "A_P$2") (pintype "passive"))
      (node (ref "U$19") (pin "3") (pinfunction "3_3") (pintype "passive"))
      (node (ref "U$2") (pin "P$1") (pinfunction "GPB0_P$1") (pintype "bidirectional"))
    )
    (net (code "55") (name "Net-(U$16-A)") (class "Default")
      (node (ref "U$16") (pin "P$2") (pinfunction "A_P$2") (pintype "passive"))
      (node (ref "U$2") (pin "P$21") (pinfunction "GPA0_P$21") (pintype "bidirectional"))
      (node (ref "U$20") (pin "5") (pinfunction "5_5") (pintype "passive"))
    )
    (net (code "56") (name "Net-(U$22-+5V)") (class "Default")
      (node (ref "U$1") (pin "RAW") (pinfunction "RAW_RAW") (pintype "bidirectional"))
      (node (ref "U$22") (pin "4") (pinfunction "+5V_4") (pintype "power_in"))
    )
    (net (code "57") (name "unconnected-(J1-Pad2)") (class "Default")
      (node (ref "J1") (pin "2") (pinfunction "2_2") (pintype "passive"))
    )
    (net (code "58") (name "unconnected-(J2-Pad2)") (class "Default")
      (node (ref "J2") (pin "2") (pinfunction "2_2") (pintype "passive"))
    )
    (net (code "59") (name "unconnected-(J3-Pad2)") (class "Default")
      (node (ref "J3") (pin "2") (pinfunction "2_2") (pintype "passive"))
    )
    (net (code "60") (name "unconnected-(J4-Pad2)") (class "Default")
      (node (ref "J4") (pin "2") (pinfunction "2_2") (pintype "passive"))
    )
    (net (code "61") (name "unconnected-(J5-Pad2)") (class "Default")
      (node (ref "J5") (pin "2") (pinfunction "2_2") (pintype "passive"))
    )
    (net (code "62") (name "unconnected-(J6-Pad2)") (class "Default")
      (node (ref "J6") (pin "2") (pinfunction "2_2") (pintype "passive"))
    )
    (net (code "63") (name "unconnected-(J7-Pad2)") (class "Default")
      (node (ref "J7") (pin "2") (pinfunction "2_2") (pintype "passive"))
    )
    (net (code "64") (name "unconnected-(J8-Pad2)") (class "Default")
      (node (ref "J8") (pin "2") (pinfunction "2_2") (pintype "passive"))
    )
    (net (code "65") (name "unconnected-(POWER-Pad9)") (class "Default")
      (node (ref "POWER") (pin "9") (pinfunction "9_9") (pintype "passive"))
    )
    (net (code "66") (name "unconnected-(U$1-Pad3.3V)") (class "Default")
      (node (ref "U$1") (pin "3.3V") (pinfunction "3.3V_3.3V") (pintype "bidirectional"))
    )
    (net (code "67") (name "unconnected-(U$1-PadA6)") (class "Default")
      (node (ref "U$1") (pin "A6") (pinfunction "A6_A6") (pintype "bidirectional"))
    )
    (net (code "68") (name "unconnected-(U$1-PadA7)") (class "Default")
      (node (ref "U$1") (pin "A7") (pinfunction "A7_A7") (pintype "bidirectional"))
    )
    (net (code "69") (name "unconnected-(U$1-PadAREF)") (class "Default")
      (node (ref "U$1") (pin "AREF") (pinfunction "AREF_AREF") (pintype "bidirectional"))
    )
    (net (code "70") (name "unconnected-(U$1-PadICSP1)") (class "Default")
      (node (ref "U$1") (pin "ICSP1") (pinfunction "ICSP1_ICSP1") (pintype "bidirectional"))
    )
    (net (code "71") (name "unconnected-(U$1-PadICSP2)") (class "Default")
      (node (ref "U$1") (pin "ICSP2") (pinfunction "ICSP2_ICSP2") (pintype "bidirectional"))
    )
    (net (code "72") (name "unconnected-(U$1-PadICSP3)") (class "Default")
      (node (ref "U$1") (pin "ICSP3") (pinfunction "ICSP3_ICSP3") (pintype "bidirectional"))
    )
    (net (code "73") (name "unconnected-(U$1-PadICSP4)") (class "Default")
      (node (ref "U$1") (pin "ICSP4") (pinfunction "ICSP4_ICSP4") (pintype "bidirectional"))
    )
    (net (code "74") (name "unconnected-(U$1-PadICSP5)") (class "Default")
      (node (ref "U$1") (pin "ICSP5") (pinfunction "ICSP5_ICSP5") (pintype "bidirectional"))
    )
    (net (code "75") (name "unconnected-(U$1-PadICSP6)") (class "Default")
      (node (ref "U$1") (pin "ICSP6") (pinfunction "ICSP6_ICSP6") (pintype "bidirectional"))
    )
    (net (code "76") (name "unconnected-(U$1-PadRST)") (class "Default")
      (node (ref "U$1") (pin "RST") (pinfunction "RST_RST") (pintype "bidirectional"))
    )
    (net (code "77") (name "unconnected-(U$1-PadRST1)") (class "Default")
      (node (ref "U$1") (pin "RST1") (pinfunction "RST1_RST1") (pintype "bidirectional"))
    )
    (net (code "78") (name "unconnected-(U$1-PadRX1)") (class "Default")
      (node (ref "U$1") (pin "RX1") (pinfunction "RX1_RX1") (pintype "bidirectional"))
    )
    (net (code "79") (name "unconnected-(U$1-PadTX0)") (class "Default")
      (node (ref "U$1") (pin "TX0") (pinfunction "TX0_TX0") (pintype "bidirectional"))
    )
    (net (code "80") (name "unconnected-(U$2-INTA-PadP$20)") (class "Default")
      (node (ref "U$2") (pin "P$20") (pinfunction "INTA_P$20") (pintype "bidirectional"))
    )
    (net (code "81") (name "unconnected-(U$2-INTB-PadP$19)") (class "Default")
      (node (ref "U$2") (pin "P$19") (pinfunction "INTB_P$19") (pintype "bidirectional"))
    )
    (net (code "82") (name "unconnected-(U$2-NC-11-PadP$11)") (class "Default")
      (node (ref "U$2") (pin "P$11") (pinfunction "NC-11_P$11") (pintype "bidirectional"))
    )
    (net (code "83") (name "unconnected-(U$2-NC-14-PadP$14)") (class "Default")
      (node (ref "U$2") (pin "P$14") (pinfunction "NC-14_P$14") (pintype "bidirectional"))
    )
    (net (code "84") (name "unconnected-(U$2-VSS-PadP$10)") (class "Default")
      (node (ref "U$2") (pin "P$10") (pinfunction "VSS_P$10") (pintype "bidirectional"))
    )
  )
)
